# ICM20608.net
KiCad netlist of a schematic drawn in Altium Designer
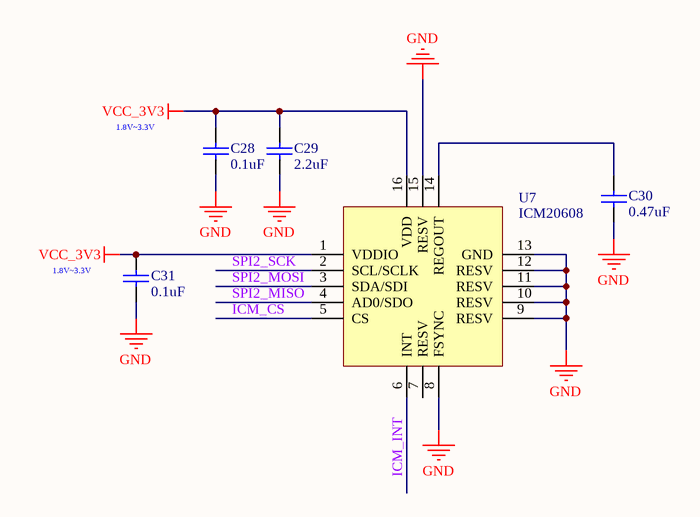
[diagram p0: ICM20608.SchDoc]

(export (version "E")
  (design (tool "Eeschema 10.0.6"))
  (components
    (comp (ref "C28")
      (value "0.1uF")
      (footprint "C0402_L")
      (description "贴片电容")
      (libsource (lib "0.1 - 电阻-电容-电感-晶振-晶体-磁珠-电位器") (part "C"))
    )
    (comp (ref "C29")
      (value "2.2uF")
      (footprint "C0402_L")
      (description "贴片电容")
      (libsource (lib "0.1 - 电阻-电容-电感-晶振-晶体-磁珠-电位器") (part "C"))
    )
    (comp (ref "C30")
      (value "0.47uF")
      (footprint "C0402_L")
      (description "贴片电容")
      (libsource (lib "0.1 - 电阻-电容-电感-晶振-晶体-磁珠-电位器") (part "C"))
    )
    (comp (ref "C31")
      (value "0.1uF")
      (footprint "C0402_L")
      (description "贴片电容")
      (libsource (lib "0.1 - 电阻-电容-电感-晶振-晶体-磁珠-电位器") (part "C"))
    )
    (comp (ref "U7")
      (value "ICM20608")
      (footprint "LGA16     3*3*0.75")
      (description "六轴姿态传感器")
      (libsource (lib "USER_Lib") (part "ICM20608-G"))
    )
  )
  (nets
    (net (code "1") (name "/ICM_CS") (class "Default")
      (node (ref "U7") (pin "5") (pinfunction "CS_5") (pintype "passive"))
    )
    (net (code "2") (name "/ICM_INT") (class "Default")
      (node (ref "U7") (pin "6") (pinfunction "INT_6") (pintype "passive"))
    )
    (net (code "3") (name "/SPI2_MISO") (class "Default")
      (node (ref "U7") (pin "4") (pinfunction "AD0/SDO_4") (pintype "passive"))
    )
    (net (code "4") (name "/SPI2_MOSI") (class "Default")
      (node (ref "U7") (pin "3") (pinfunction "SDA/SDI_3") (pintype "passive"))
    )
    (net (code "5") (name "/SPI2_SCK") (class "Default")
      (node (ref "U7") (pin "2") (pinfunction "SCL/SCLK_2") (pintype "passive"))
    )
    (net (code "6") (name "GND") (class "Default")
      (node (ref "C28") (pin "1") (pinfunction "1_1") (pintype "passive"))
      (node (ref "C29") (pin "1") (pinfunction "1_1") (pintype "passive"))
      (node (ref "C30") (pin "2") (pinfunction "2_2") (pintype "passive"))
      (node (ref "C31") (pin "2") (pinfunction "2_2") (pintype "passive"))
      (node (ref "U7") (pin "10") (pinfunction "RESV_10") (pintype "passive"))
      (node (ref "U7") (pin "11") (pinfunction "RESV_11") (pintype "passive"))
      (node (ref "U7") (pin "12") (pinfunction "RESV_12") (pintype "passive"))
      (node (ref "U7") (pin "13") (pinfunction "GND_13") (pintype "passive"))
      (node (ref "U7") (pin "15") (pinfunction "RESV_15") (pintype "passive"))
      (node (ref "U7") (pin "8") (pinfunction "FSYNC_8") (pintype "passive"))
      (node (ref "U7") (pin "9") (pinfunction "RESV_9") (pintype "passive"))
    )
    (net (code "7") (name "Net-(U7-REGOUT)") (class "Default")
      (node (ref "C30") (pin "1") (pinfunction "1_1") (pintype "passive"))
      (node (ref "U7") (pin "14") (pinfunction "REGOUT_14") (pintype "passive"))
    )
    (net (code "8") (name "VCC_3V3") (class "Default")
      (node (ref "C28") (pin "2") (pinfunction "2_2") (pintype "passive"))
      (node (ref "C29") (pin "2") (pinfunction "2_2") (pintype "passive"))
      (node (ref "C31") (pin "1") (pinfunction "1_1") (pintype "passive"))
      (node (ref "U7") (pin "1") (pinfunction "VDDIO_1") (pintype "passive"))
      (node (ref "U7") (pin "16") (pinfunction "VDD_16") (pintype "passive"))
    )
    (net (code "9") (name "unconnected-(U7-RESV-Pad7)") (class "Default")
      (node (ref "U7") (pin "7") (pinfunction "RESV_7") (pintype "passive"))
    )
  )
)
